# SCH.net
KiCad netlist of a schematic drawn in EasyEDA
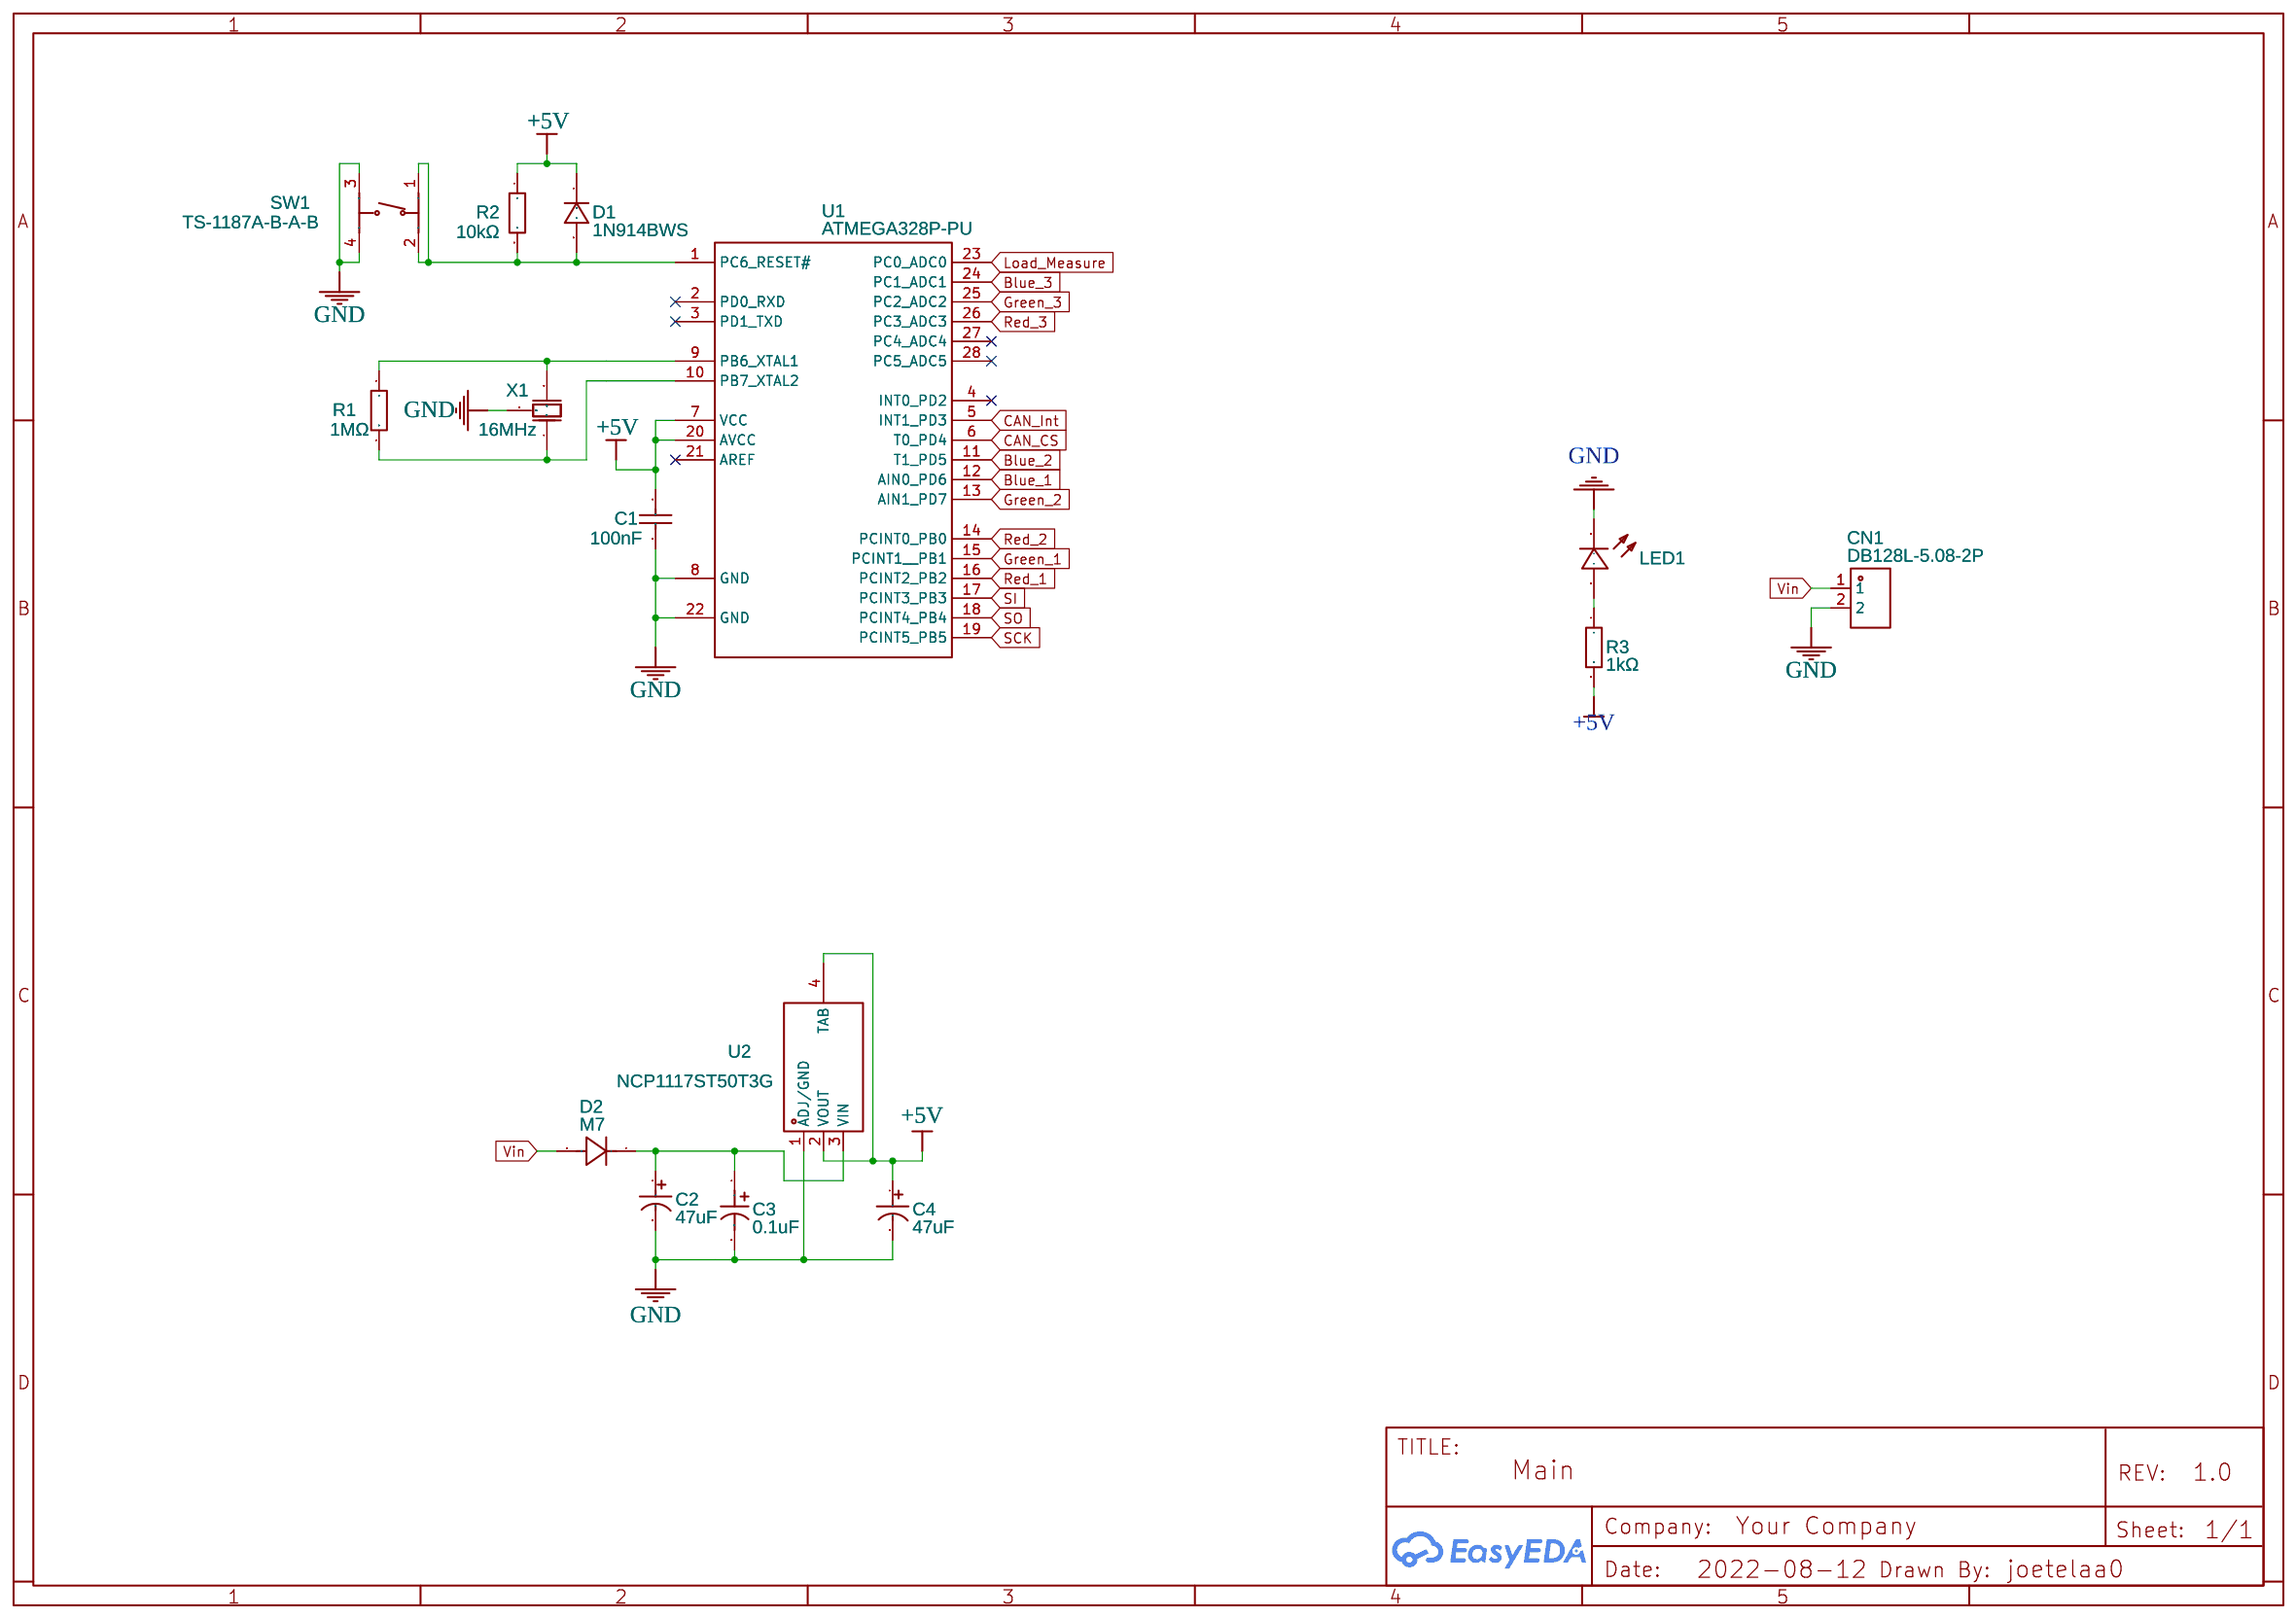
[diagram p0: Main]
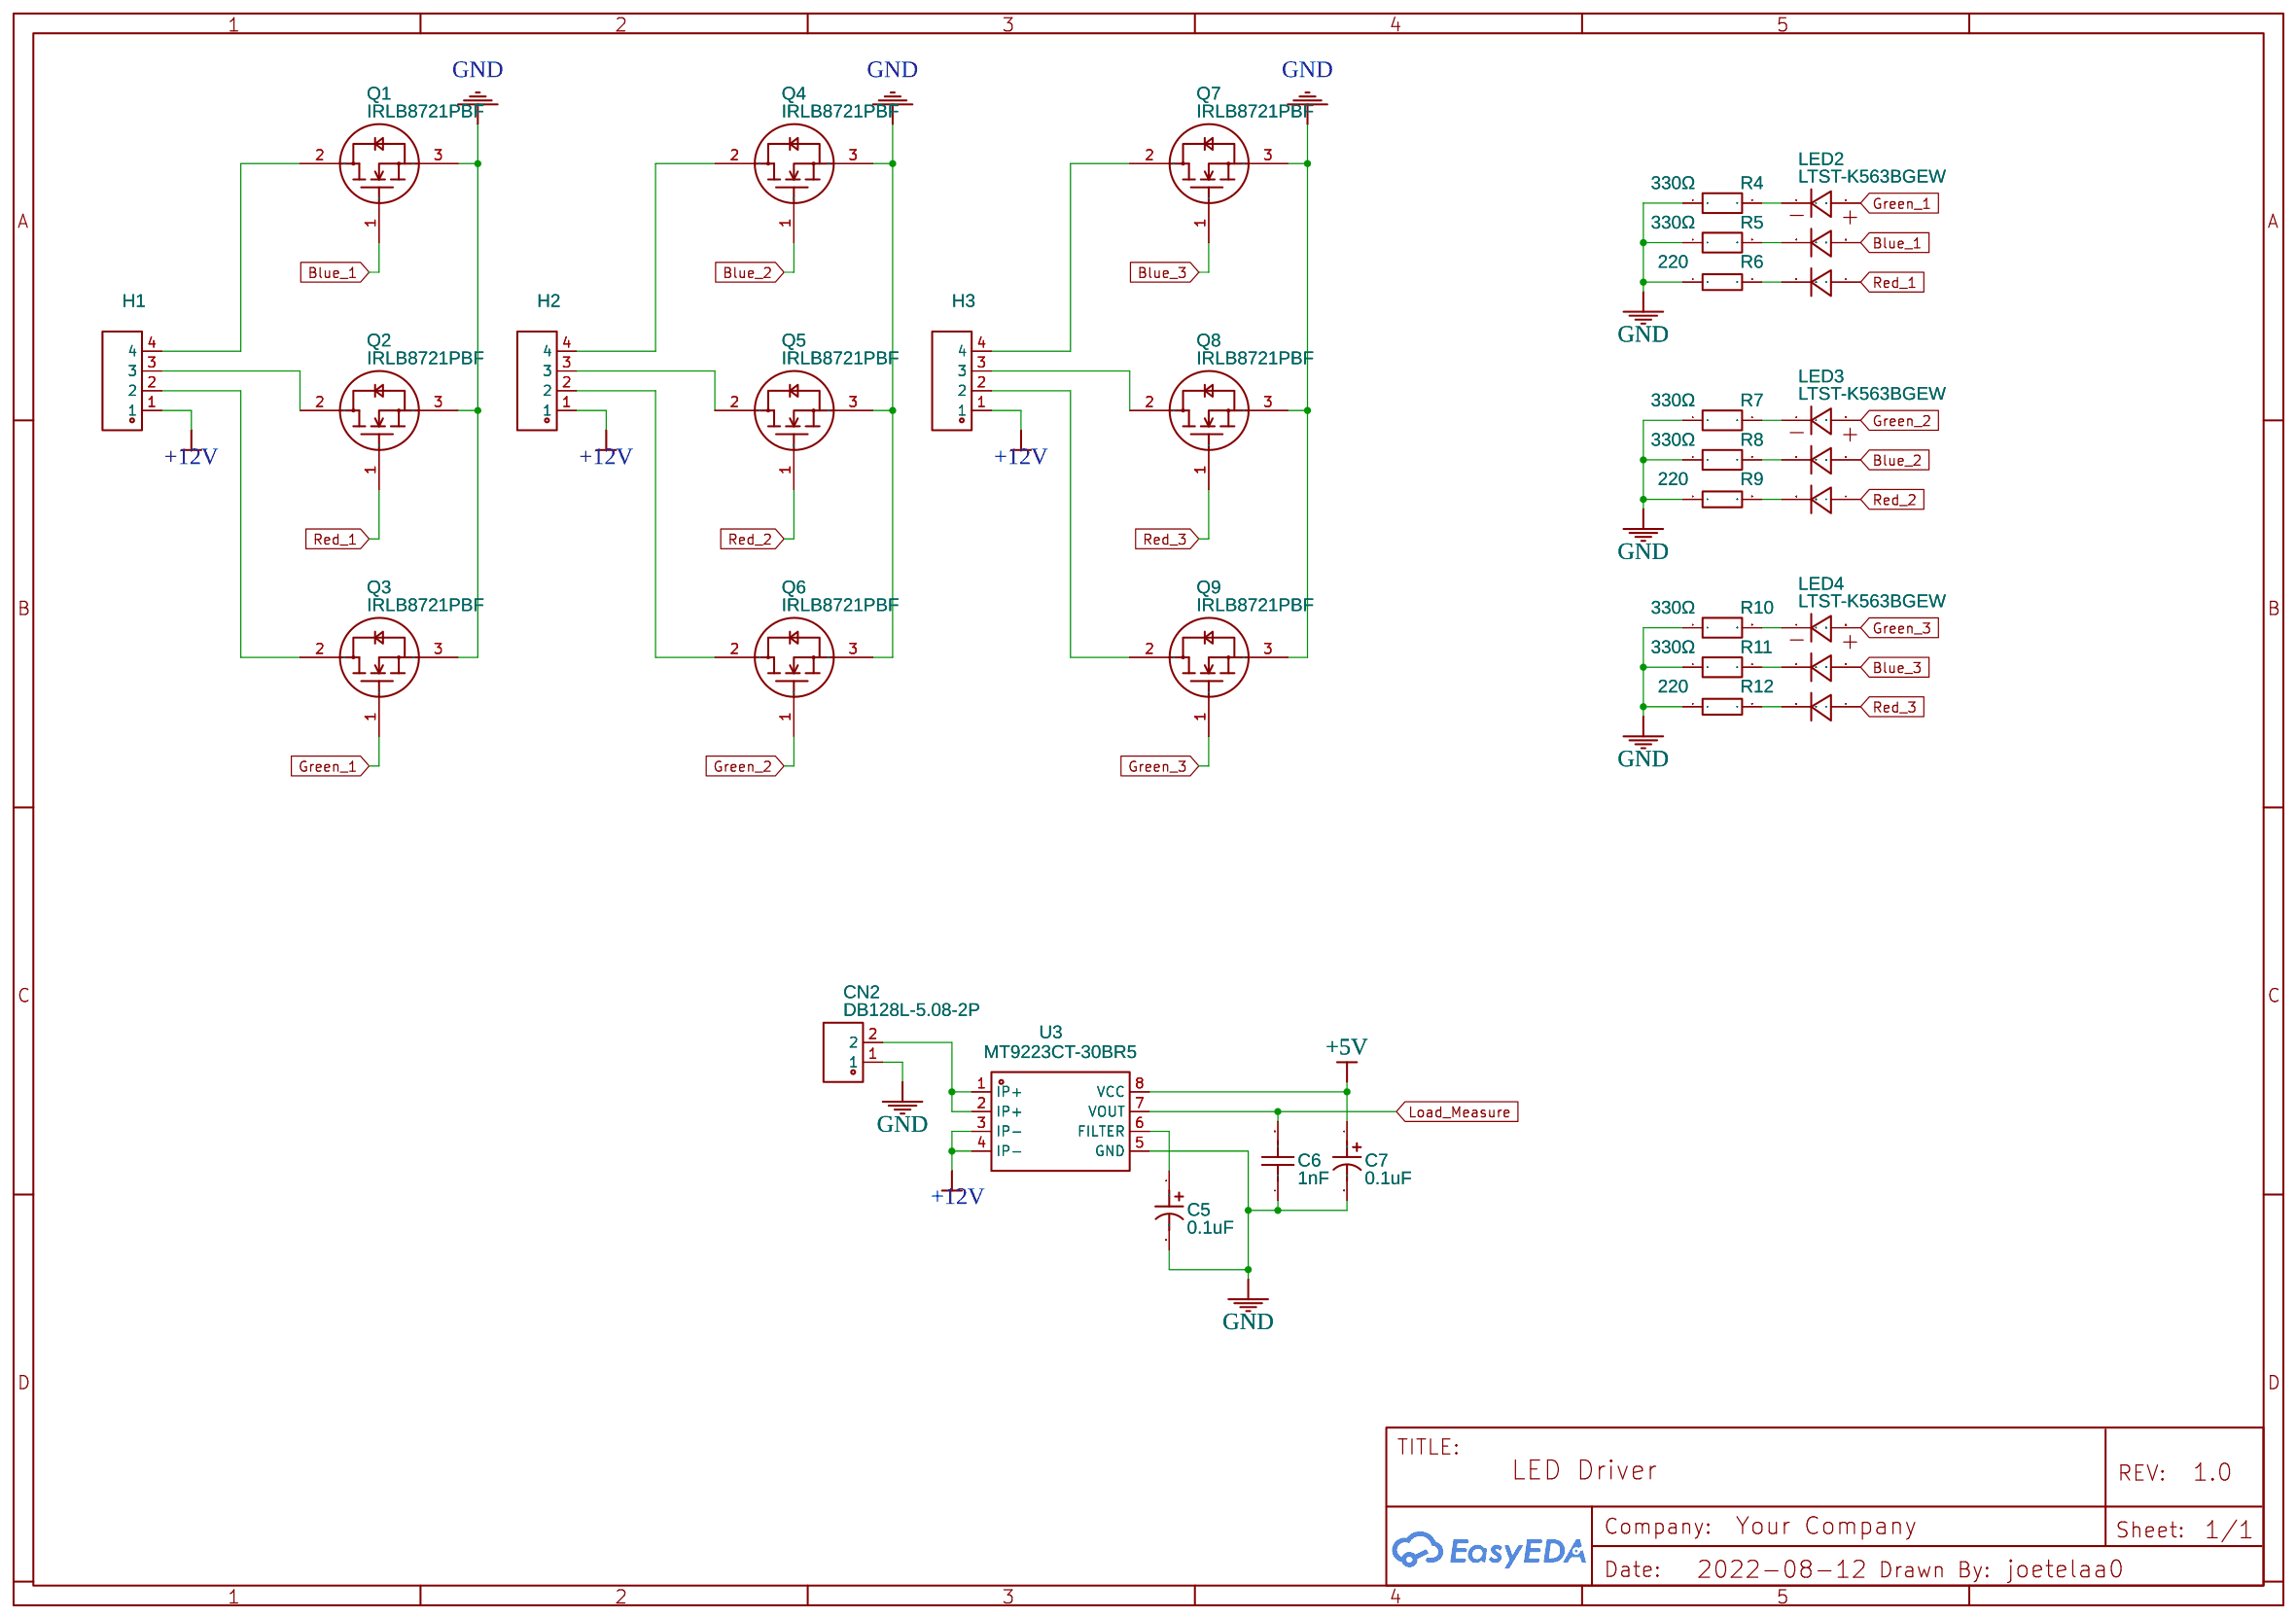
[diagram p1: LED Driver]
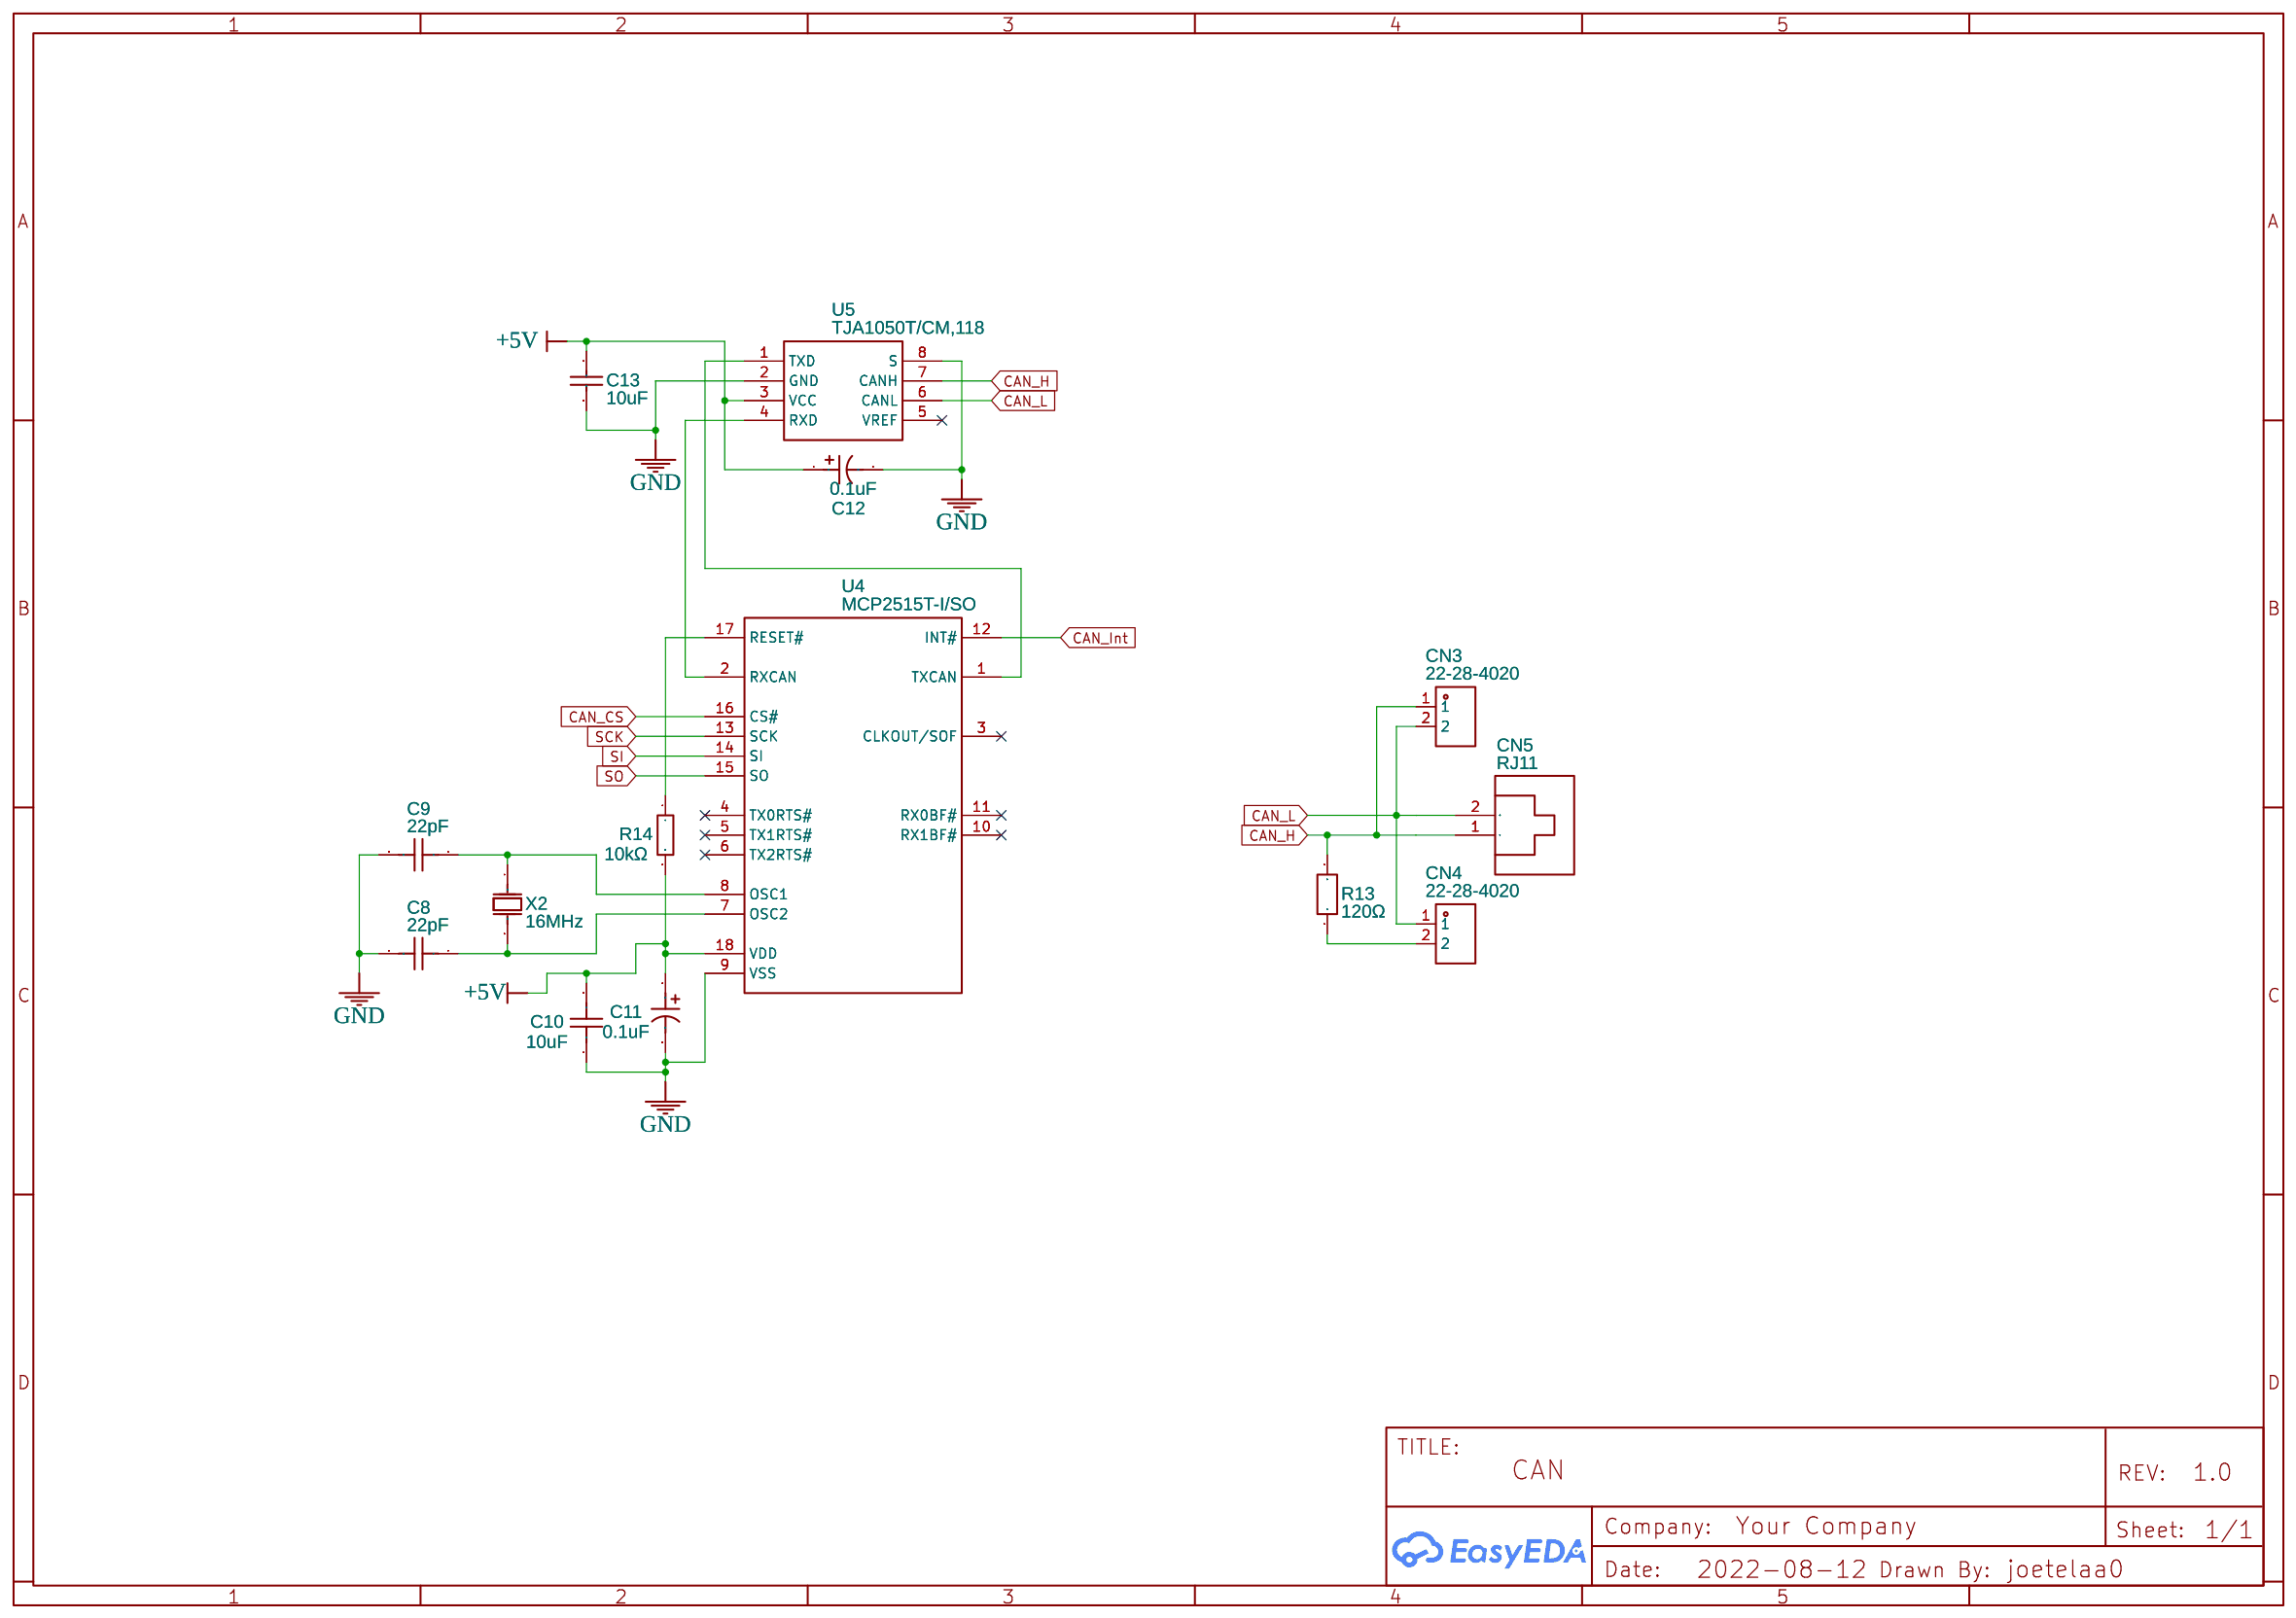
[diagram p2: CAN]

(export (version "E")
  (design (tool "Eeschema 10.0.6"))
  (components
    (comp (ref "C1")
      (value "100nF")
      (fields
        (field (name "BOM_Manufacturer Part") "FN18X104K500PBG")
        (field (name "BOM_Supplier Part") "C235731")
      )
      (libsource (lib "") (part "FN18X104K500PBG"))
    )
    (comp (ref "C2")
      (value "47uF")
      (fields
        (field (name "BOM_Manufacturer Part") "RVT1V470M0605")
        (field (name "BOM_Supplier Part") "C72522")
      )
      (libsource (lib "") (part "RVT1V470M0605_c72522"))
    )
    (comp (ref "C3")
      (value "0.1uF")
      (fields
        (field (name "BOM_Manufacturer Part") "CA45A-A-35V-0.1UF-K")
        (field (name "BOM_Supplier Part") "C2976899")
      )
      (libsource (lib "") (part "CA45A-A-35V-0.1UF-K"))
    )
    (comp (ref "C4")
      (value "47uF")
      (fields
        (field (name "BOM_Manufacturer Part") "RVT1V470M0605")
        (field (name "BOM_Supplier Part") "C72522")
      )
      (libsource (lib "") (part "RVT1V470M0605_c72522"))
    )
    (comp (ref "CN1")
      (value "DB128L-5.08-2P")
      (fields (field (name "BOM_Supplier Part") "C395868"))
      (libsource (lib "") (part "DB128L-5.08-2P"))
    )
    (comp (ref "D1")
      (value "1N914BWS")
      (fields (field (name "BOM_Supplier Part") "C258181"))
      (libsource (lib "") (part "1N914BWS"))
    )
    (comp (ref "D2")
      (value "M7")
      (fields (field (name "BOM_Manufacturer Part") "1N4007") (field (name "BOM_Supplier Part") "C727081"))
      (libsource (lib "") (part "1N4007_C727081"))
    )
    (comp (ref "LED1")
      (value "FC-1608GHK-570A08")
      (fields (field (name "BOM_Supplier Part") "C193901"))
      (libsource (lib "") (part "FC-1608GHK-570A08"))
    )
    (comp (ref "R1")
      (value "1MΩ")
      (fields
        (field (name "BOM_Manufacturer Part") "ERJ-3EKF1004V")
        (field (name "BOM_Supplier Part") "C193390")
      )
      (libsource (lib "") (part "ERJ-3EKF1004V"))
    )
    (comp (ref "R2")
      (value "10kΩ")
      (fields
        (field (name "BOM_Manufacturer Part") "RMS06FT1002")
        (field (name "BOM_Supplier Part") "C209013")
      )
      (libsource (lib "") (part "RMS06FT1002"))
    )
    (comp (ref "R3")
      (value "1kΩ")
      (fields
        (field (name "BOM_Manufacturer Part") "TR0603B1KP0525")
        (field (name "BOM_Supplier Part") "C188364")
      )
      (libsource (lib "") (part "TR0603B1KP0525"))
    )
    (comp (ref "SW1")
      (value "TS-1187A-B-A-B")
      (fields (field (name "BOM_Supplier Part") "C318884"))
      (libsource (lib "") (part "TS-1187A-B-A-B"))
    )
    (comp (ref "U1")
      (value "ATMEGA328P-PU")
      (fields (field (name "BOM_Supplier Part") "C33901"))
      (libsource (lib "") (part "ATMEGA328P-PU"))
    )
    (comp (ref "U2")
      (value "NCP1117ST50T3G")
      (fields (field (name "BOM_Supplier Part") "C17314"))
      (libsource (lib "") (part "NCP1117ST50T3G"))
    )
    (comp (ref "X1")
      (value "16MHz")
      (fields
        (field (name "BOM_Manufacturer Part") "CSTNE16M0V53C000R0")
        (field (name "BOM_Supplier Part") "C882606")
      )
      (libsource (lib "") (part "CSTNE16M0V53C000R0"))
    )
    (comp (ref "C5")
      (value "0.1uF")
      (fields
        (field (name "BOM_Manufacturer Part") "CA45A-A-35V-0.1UF-K")
        (field (name "BOM_Supplier Part") "C2976899")
      )
      (libsource (lib "") (part "CA45A-A-35V-0.1UF-K"))
    )
    (comp (ref "C6")
      (value "1nF")
      (fields
        (field (name "BOM_Manufacturer Part") "GRM1885C1H102JA01D")
        (field (name "BOM_Supplier Part") "C77026")
      )
      (libsource (lib "") (part "GRM1885C1H102JA01D"))
    )
    (comp (ref "C7")
      (value "0.1uF")
      (fields
        (field (name "BOM_Manufacturer Part") "CA45A-A-35V-0.1UF-K")
        (field (name "BOM_Supplier Part") "C2976899")
      )
      (libsource (lib "") (part "CA45A-A-35V-0.1UF-K"))
    )
    (comp (ref "CN2")
      (value "DB128L-5.08-2P")
      (fields (field (name "BOM_Supplier Part") "C395868"))
      (libsource (lib "") (part "DB128L-5.08-2P"))
    )
    (comp (ref "H1")
      (value "X6511WV-04H-C30D60")
      (fields (field (name "BOM_Supplier Part") "C706876"))
      (libsource (lib "") (part "X6511WV-04H-C30D60"))
    )
    (comp (ref "H2")
      (value "X6511WV-04H-C30D60")
      (fields (field (name "BOM_Supplier Part") "C706876"))
      (libsource (lib "") (part "X6511WV-04H-C30D60"))
    )
    (comp (ref "H3")
      (value "X6511WV-04H-C30D60")
      (fields (field (name "BOM_Supplier Part") "C706876"))
      (libsource (lib "") (part "X6511WV-04H-C30D60"))
    )
    (comp (ref "LED2")
      (value "LTST-K563BGEW")
      (fields (field (name "BOM_Supplier Part") "C284911"))
      (libsource (lib "") (part "LTST-K563BGEW"))
    )
    (comp (ref "LED3")
      (value "LTST-K563BGEW")
      (fields (field (name "BOM_Supplier Part") "C284911"))
      (libsource (lib "") (part "LTST-K563BGEW"))
    )
    (comp (ref "LED4")
      (value "LTST-K563BGEW")
      (fields (field (name "BOM_Supplier Part") "C284911"))
      (libsource (lib "") (part "LTST-K563BGEW"))
    )
    (comp (ref "Q1")
      (value "IRLB8721PBF")
      (fields (field (name "BOM_Supplier Part") "C153222"))
      (libsource (lib "") (part "IRLB8721PBF"))
    )
    (comp (ref "Q2")
      (value "IRLB8721PBF")
      (fields (field (name "BOM_Supplier Part") "C153222"))
      (libsource (lib "") (part "IRLB8721PBF"))
    )
    (comp (ref "Q3")
      (value "IRLB8721PBF")
      (fields (field (name "BOM_Supplier Part") "C153222"))
      (libsource (lib "") (part "IRLB8721PBF"))
    )
    (comp (ref "Q4")
      (value "IRLB8721PBF")
      (fields (field (name "BOM_Supplier Part") "C153222"))
      (libsource (lib "") (part "IRLB8721PBF"))
    )
    (comp (ref "Q5")
      (value "IRLB8721PBF")
      (fields (field (name "BOM_Supplier Part") "C153222"))
      (libsource (lib "") (part "IRLB8721PBF"))
    )
    (comp (ref "Q6")
      (value "IRLB8721PBF")
      (fields (field (name "BOM_Supplier Part") "C153222"))
      (libsource (lib "") (part "IRLB8721PBF"))
    )
    (comp (ref "Q7")
      (value "IRLB8721PBF")
      (fields (field (name "BOM_Supplier Part") "C153222"))
      (libsource (lib "") (part "IRLB8721PBF"))
    )
    (comp (ref "Q8")
      (value "IRLB8721PBF")
      (fields (field (name "BOM_Supplier Part") "C153222"))
      (libsource (lib "") (part "IRLB8721PBF"))
    )
    (comp (ref "Q9")
      (value "IRLB8721PBF")
      (fields (field (name "BOM_Supplier Part") "C153222"))
      (libsource (lib "") (part "IRLB8721PBF"))
    )
    (comp (ref "R4")
      (value "330Ω")
      (fields
        (field (name "BOM_Manufacturer Part") "FRC0603F3300TS")
        (field (name "BOM_Supplier Part") "C2933198")
      )
      (libsource (lib "") (part "FRC0603F3300TS"))
    )
    (comp (ref "R5")
      (value "330Ω")
      (fields
        (field (name "BOM_Manufacturer Part") "FRC0603F3300TS")
        (field (name "BOM_Supplier Part") "C2933198")
      )
      (libsource (lib "") (part "FRC0603F3300TS"))
    )
    (comp (ref "R6")
      (value "220")
      (fields
        (field (name "BOM_Manufacturer Part") "AF0603FR-07220RL")
        (field (name "BOM_Supplier Part") "C144094")
      )
      (libsource (lib "") (part "AF0603FR-07220RL"))
    )
    (comp (ref "R7")
      (value "330Ω")
      (fields
        (field (name "BOM_Manufacturer Part") "FRC0603F3300TS")
        (field (name "BOM_Supplier Part") "C2933198")
      )
      (libsource (lib "") (part "FRC0603F3300TS"))
    )
    (comp (ref "R8")
      (value "330Ω")
      (fields
        (field (name "BOM_Manufacturer Part") "FRC0603F3300TS")
        (field (name "BOM_Supplier Part") "C2933198")
      )
      (libsource (lib "") (part "FRC0603F3300TS"))
    )
    (comp (ref "R9")
      (value "220")
      (fields
        (field (name "BOM_Manufacturer Part") "AF0603FR-07220RL")
        (field (name "BOM_Supplier Part") "C144094")
      )
      (libsource (lib "") (part "AF0603FR-07220RL"))
    )
    (comp (ref "R10")
      (value "330Ω")
      (fields
        (field (name "BOM_Manufacturer Part") "FRC0603F3300TS")
        (field (name "BOM_Supplier Part") "C2933198")
      )
      (libsource (lib "") (part "FRC0603F3300TS"))
    )
    (comp (ref "R11")
      (value "330Ω")
      (fields
        (field (name "BOM_Manufacturer Part") "FRC0603F3300TS")
        (field (name "BOM_Supplier Part") "C2933198")
      )
      (libsource (lib "") (part "FRC0603F3300TS"))
    )
    (comp (ref "R12")
      (value "220")
      (fields
        (field (name "BOM_Manufacturer Part") "AF0603FR-07220RL")
        (field (name "BOM_Supplier Part") "C144094")
      )
      (libsource (lib "") (part "AF0603FR-07220RL"))
    )
    (comp (ref "U3")
      (value "MT9223CT-30BR5")
      (fields (field (name "BOM_Supplier Part") "C879636"))
      (libsource (lib "") (part "MT9223CT-30BR5"))
    )
    (comp (ref "C8")
      (value "22pF")
      (fields
        (field (name "BOM_Manufacturer Part") "CGA3E2C0G1H220JT0Y0N")
        (field (name "BOM_Supplier Part") "C338053")
      )
      (libsource (lib "") (part "CGA3E2C0G1H220JT0Y0N"))
    )
    (comp (ref "C9")
      (value "22pF")
      (fields
        (field (name "BOM_Manufacturer Part") "CGA3E2C0G1H220JT0Y0N")
        (field (name "BOM_Supplier Part") "C338053")
      )
      (libsource (lib "") (part "CGA3E2C0G1H220JT0Y0N"))
    )
    (comp (ref "C10")
      (value "10uF")
      (fields
        (field (name "BOM_Manufacturer Part") "JMK316AB7106KLHT")
        (field (name "BOM_Supplier Part") "C454108")
      )
      (libsource (lib "") (part "JMK316AB7106KLHT"))
    )
    (comp (ref "C11")
      (value "0.1uF")
      (fields
        (field (name "BOM_Manufacturer Part") "CA45A-A-35V-0.1UF-K")
        (field (name "BOM_Supplier Part") "C2976899")
      )
      (libsource (lib "") (part "CA45A-A-35V-0.1UF-K"))
    )
    (comp (ref "C12")
      (value "0.1uF")
      (fields
        (field (name "BOM_Manufacturer Part") "CA45A-A-35V-0.1UF-K")
        (field (name "BOM_Supplier Part") "C2976899")
      )
      (libsource (lib "") (part "CA45A-A-35V-0.1UF-K_1"))
    )
    (comp (ref "C13")
      (value "10uF")
      (fields
        (field (name "BOM_Manufacturer Part") "JMK107BJ106MA-T")
        (field (name "BOM_Supplier Part") "C87152")
      )
      (libsource (lib "") (part "JMK107BJ106MA-T"))
    )
    (comp (ref "CN3")
      (value "22-28-4020")
      (fields (field (name "BOM_Supplier Part") "C234182"))
      (libsource (lib "") (part "22-28-4020"))
    )
    (comp (ref "CN4")
      (value "22-28-4020")
      (fields (field (name "BOM_Supplier Part") "C234182"))
      (libsource (lib "") (part "22-28-4020"))
    )
    (comp (ref "CN5")
      (value "RJ11")
      (fields (field (name "BOM_Supplier Part") "C189745"))
      (libsource (lib "") (part "PCB-6P2C-90_C189745"))
    )
    (comp (ref "R13")
      (value "120Ω")
      (fields
        (field (name "BOM_Manufacturer Part") "ERJPA3J121V")
        (field (name "BOM_Supplier Part") "C445808")
      )
      (libsource (lib "") (part "ERJPA3J121V"))
    )
    (comp (ref "R14")
      (value "10kΩ")
      (fields
        (field (name "BOM_Manufacturer Part") "RMS06FT1002")
        (field (name "BOM_Supplier Part") "C209013")
      )
      (libsource (lib "") (part "RMS06FT1002"))
    )
    (comp (ref "U4")
      (value "MCP2515T-I/SO")
      (fields (field (name "BOM_Supplier Part") "C153782"))
      (libsource (lib "") (part "MCP2515T-I/SO"))
    )
    (comp (ref "U5")
      (value "TJA1050T/CM,118")
      (fields (field (name "BOM_Supplier Part") "C6952"))
      (libsource (lib "") (part "TJA1050T/CM,118"))
    )
    (comp (ref "X2")
      (value "16MHz")
      (fields
        (field (name "BOM_Manufacturer Part") "X49SD16MSD2SC")
        (field (name "BOM_Supplier Part") "C16212")
      )
      (libsource (lib "") (part "X49SD16MSD2SC"))
    )
  )
  (nets
    (net (code "1") (name "+5V") (class "Default")
      (node (ref "C1") (pin "2") (pinfunction "2_2") (pintype "input"))
      (node (ref "C10") (pin "2") (pinfunction "2_2") (pintype "unspecified"))
      (node (ref "C11") (pin "1") (pinfunction "1_1") (pintype "input"))
      (node (ref "C12") (pin "1") (pinfunction "1_1") (pintype "input"))
      (node (ref "C13") (pin "2") (pinfunction "2_2") (pintype "input"))
      (node (ref "C4") (pin "1") (pinfunction "1_1") (pintype "input"))
      (node (ref "C7") (pin "1") (pinfunction "1_1") (pintype "input"))
      (node (ref "D1") (pin "1") (pinfunction "C_1") (pintype "unspecified"))
      (node (ref "R14") (pin "2") (pinfunction "2_2") (pintype "unspecified"))
      (node (ref "R2") (pin "1") (pinfunction "1_1") (pintype "unspecified"))
      (node (ref "R3") (pin "2") (pinfunction "2_2") (pintype "unspecified"))
      (node (ref "U1") (pin "20") (pinfunction "AVCC_20") (pintype "passive"))
      (node (ref "U1") (pin "7") (pinfunction "VCC_7") (pintype "passive"))
      (node (ref "U2") (pin "2") (pinfunction "VOUT_2") (pintype "unspecified"))
      (node (ref "U2") (pin "4") (pinfunction "TAB_4") (pintype "unspecified"))
      (node (ref "U3") (pin "8") (pinfunction "VCC_8") (pintype "unspecified"))
      (node (ref "U4") (pin "18") (pinfunction "VDD_18") (pintype "passive"))
      (node (ref "U5") (pin "3") (pinfunction "VCC_3") (pintype "unspecified"))
    )
    (net (code "2") (name "+12V") (class "Default")
      (node (ref "H1") (pin "1") (pinfunction "1_1") (pintype "unspecified"))
      (node (ref "H2") (pin "1") (pinfunction "1_1") (pintype "unspecified"))
      (node (ref "H3") (pin "1") (pinfunction "1_1") (pintype "unspecified"))
      (node (ref "U3") (pin "3") (pinfunction "IP-_3") (pintype "unspecified"))
      (node (ref "U3") (pin "4") (pinfunction "IP-_4") (pintype "unspecified"))
    )
    (net (code "3") (name "Blue_1") (class "Default")
      (node (ref "LED2") (pin "5") (pinfunction "5_5") (pintype "unspecified"))
      (node (ref "Q1") (pin "1") (pinfunction "G_1") (pintype "unspecified"))
      (node (ref "U1") (pin "12") (pinfunction "AIN0_PD6_12") (pintype "bidirectional"))
    )
    (net (code "4") (name "Blue_2") (class "Default")
      (node (ref "LED3") (pin "5") (pinfunction "5_5") (pintype "unspecified"))
      (node (ref "Q4") (pin "1") (pinfunction "G_1") (pintype "unspecified"))
      (node (ref "U1") (pin "11") (pinfunction "T1_PD5_11") (pintype "bidirectional"))
    )
    (net (code "5") (name "Blue_3") (class "Default")
      (node (ref "LED4") (pin "5") (pinfunction "5_5") (pintype "unspecified"))
      (node (ref "Q7") (pin "1") (pinfunction "G_1") (pintype "unspecified"))
      (node (ref "U1") (pin "24") (pinfunction "PC1_ADC1_24") (pintype "bidirectional"))
    )
    (net (code "6") (name "CAN_CS") (class "Default")
      (node (ref "U1") (pin "6") (pinfunction "T0_PD4_6") (pintype "bidirectional"))
      (node (ref "U4") (pin "16") (pinfunction "CS#_16") (pintype "unspecified"))
    )
    (net (code "7") (name "CAN_H") (class "Default")
      (node (ref "CN3") (pin "1") (pinfunction "1_1") (pintype "unspecified"))
      (node (ref "CN5") (pin "1") (pinfunction "1_1") (pintype "unspecified"))
      (node (ref "R13") (pin "2") (pinfunction "2_2") (pintype "unspecified"))
      (node (ref "U5") (pin "7") (pinfunction "CANH_7") (pintype "unspecified"))
    )
    (net (code "8") (name "CAN_Int") (class "Default")
      (node (ref "U1") (pin "5") (pinfunction "INT1_PD3_5") (pintype "bidirectional"))
      (node (ref "U4") (pin "12") (pinfunction "INT#_12") (pintype "output"))
    )
    (net (code "9") (name "CAN_L") (class "Default")
      (node (ref "CN3") (pin "2") (pinfunction "2_2") (pintype "unspecified"))
      (node (ref "CN4") (pin "1") (pinfunction "1_1") (pintype "unspecified"))
      (node (ref "CN5") (pin "2") (pinfunction "2_2") (pintype "unspecified"))
      (node (ref "U5") (pin "6") (pinfunction "CANL_6") (pintype "unspecified"))
    )
    (net (code "10") (name "GND") (class "Default")
      (node (ref "C1") (pin "1") (pinfunction "1_1") (pintype "input"))
      (node (ref "C10") (pin "1") (pinfunction "1_1") (pintype "unspecified"))
      (node (ref "C11") (pin "2") (pinfunction "2_2") (pintype "input"))
      (node (ref "C12") (pin "2") (pinfunction "2_2") (pintype "input"))
      (node (ref "C13") (pin "1") (pinfunction "1_1") (pintype "input"))
      (node (ref "C2") (pin "2") (pinfunction "2_2") (pintype "input"))
      (node (ref "C3") (pin "2") (pinfunction "2_2") (pintype "input"))
      (node (ref "C4") (pin "2") (pinfunction "2_2") (pintype "input"))
      (node (ref "C5") (pin "2") (pinfunction "2_2") (pintype "input"))
      (node (ref "C6") (pin "1") (pinfunction "1_1") (pintype "unspecified"))
      (node (ref "C7") (pin "2") (pinfunction "2_2") (pintype "input"))
      (node (ref "C8") (pin "2") (pinfunction "2_2") (pintype "unspecified"))
      (node (ref "C9") (pin "2") (pinfunction "2_2") (pintype "unspecified"))
      (node (ref "CN1") (pin "2") (pinfunction "2_2") (pintype "unspecified"))
      (node (ref "CN2") (pin "1") (pinfunction "1_1") (pintype "unspecified"))
      (node (ref "LED1") (pin "2") (pinfunction "-_2") (pintype "unspecified"))
      (node (ref "Q1") (pin "3") (pinfunction "S_3") (pintype "unspecified"))
      (node (ref "Q2") (pin "3") (pinfunction "S_3") (pintype "unspecified"))
      (node (ref "Q3") (pin "3") (pinfunction "S_3") (pintype "unspecified"))
      (node (ref "Q4") (pin "3") (pinfunction "S_3") (pintype "unspecified"))
      (node (ref "Q5") (pin "3") (pinfunction "S_3") (pintype "unspecified"))
      (node (ref "Q6") (pin "3") (pinfunction "S_3") (pintype "unspecified"))
      (node (ref "Q7") (pin "3") (pinfunction "S_3") (pintype "unspecified"))
      (node (ref "Q8") (pin "3") (pinfunction "S_3") (pintype "unspecified"))
      (node (ref "Q9") (pin "3") (pinfunction "S_3") (pintype "unspecified"))
      (node (ref "R10") (pin "1") (pinfunction "1_1") (pintype "unspecified"))
      (node (ref "R11") (pin "1") (pinfunction "1_1") (pintype "unspecified"))
      (node (ref "R12") (pin "1") (pinfunction "1_1") (pintype "unspecified"))
      (node (ref "R4") (pin "1") (pinfunction "1_1") (pintype "unspecified"))
      (node (ref "R5") (pin "1") (pinfunction "1_1") (pintype "unspecified"))
      (node (ref "R6") (pin "1") (pinfunction "1_1") (pintype "unspecified"))
      (node (ref "R7") (pin "1") (pinfunction "1_1") (pintype "unspecified"))
      (node (ref "R8") (pin "1") (pinfunction "1_1") (pintype "unspecified"))
      (node (ref "R9") (pin "1") (pinfunction "1_1") (pintype "unspecified"))
      (node (ref "SW1") (pin "3") (pinfunction "C_3") (pintype "unspecified"))
      (node (ref "SW1") (pin "4") (pinfunction "D_4") (pintype "unspecified"))
      (node (ref "U1") (pin "22") (pinfunction "GND_22") (pintype "passive"))
      (node (ref "U1") (pin "8") (pinfunction "GND_8") (pintype "passive"))
      (node (ref "U2") (pin "1") (pinfunction "ADJ/GND_1") (pintype "unspecified"))
      (node (ref "U3") (pin "5") (pinfunction "GND_5") (pintype "unspecified"))
      (node (ref "U4") (pin "9") (pinfunction "VSS_9") (pintype "passive"))
      (node (ref "U5") (pin "2") (pinfunction "GND_2") (pintype "unspecified"))
      (node (ref "U5") (pin "8") (pinfunction "S_8") (pintype "unspecified"))
      (node (ref "X1") (pin "2") (pinfunction "GND_2") (pintype "input"))
    )
    (net (code "11") (name "Green_1") (class "Default")
      (node (ref "LED2") (pin "6") (pinfunction "6_6") (pintype "unspecified"))
      (node (ref "Q3") (pin "1") (pinfunction "G_1") (pintype "unspecified"))
      (node (ref "U1") (pin "15") (pinfunction "PCINT1__PB1_15") (pintype "bidirectional"))
    )
    (net (code "12") (name "Green_2") (class "Default")
      (node (ref "LED3") (pin "6") (pinfunction "6_6") (pintype "unspecified"))
      (node (ref "Q6") (pin "1") (pinfunction "G_1") (pintype "unspecified"))
      (node (ref "U1") (pin "13") (pinfunction "AIN1_PD7_13") (pintype "bidirectional"))
    )
    (net (code "13") (name "Green_3") (class "Default")
      (node (ref "LED4") (pin "6") (pinfunction "6_6") (pintype "unspecified"))
      (node (ref "Q9") (pin "1") (pinfunction "G_1") (pintype "unspecified"))
      (node (ref "U1") (pin "25") (pinfunction "PC2_ADC2_25") (pintype "bidirectional"))
    )
    (net (code "14") (name "Load_Measure") (class "Default")
      (node (ref "C6") (pin "2") (pinfunction "2_2") (pintype "unspecified"))
      (node (ref "U1") (pin "23") (pinfunction "PC0_ADC0_23") (pintype "bidirectional"))
      (node (ref "U3") (pin "7") (pinfunction "VOUT_7") (pintype "unspecified"))
    )
    (net (code "15") (name "Net-(CN2-Pad2)") (class "Default")
      (node (ref "CN2") (pin "2") (pinfunction "2_2") (pintype "unspecified"))
      (node (ref "U3") (pin "1") (pinfunction "IP+_1") (pintype "unspecified"))
      (node (ref "U3") (pin "2") (pinfunction "IP+_2") (pintype "unspecified"))
    )
    (net (code "16") (name "Net-(CN4-Pad2)") (class "Default")
      (node (ref "CN4") (pin "2") (pinfunction "2_2") (pintype "unspecified"))
      (node (ref "R13") (pin "1") (pinfunction "1_1") (pintype "unspecified"))
    )
    (net (code "17") (name "Net-(D1-A)") (class "Default")
      (node (ref "D1") (pin "2") (pinfunction "A_2") (pintype "unspecified"))
      (node (ref "R2") (pin "2") (pinfunction "2_2") (pintype "unspecified"))
      (node (ref "SW1") (pin "1") (pinfunction "A_1") (pintype "unspecified"))
      (node (ref "SW1") (pin "2") (pinfunction "B_2") (pintype "unspecified"))
      (node (ref "U1") (pin "1") (pinfunction "PC6_RESET#_1") (pintype "bidirectional"))
    )
    (net (code "18") (name "Net-(D2-K)") (class "Default")
      (node (ref "C2") (pin "1") (pinfunction "1_1") (pintype "input"))
      (node (ref "C3") (pin "1") (pinfunction "1_1") (pintype "input"))
      (node (ref "D2") (pin "1") (pinfunction "K_1") (pintype "unspecified"))
      (node (ref "U2") (pin "3") (pinfunction "VIN_3") (pintype "unspecified"))
    )
    (net (code "19") (name "Net-(LED1-+)") (class "Default")
      (node (ref "LED1") (pin "1") (pinfunction "+_1") (pintype "unspecified"))
      (node (ref "R3") (pin "1") (pinfunction "1_1") (pintype "unspecified"))
    )
    (net (code "20") (name "Net-(LED2-Pad1)") (class "Default")
      (node (ref "LED2") (pin "1") (pinfunction "1_1") (pintype "unspecified"))
      (node (ref "R4") (pin "2") (pinfunction "2_2") (pintype "unspecified"))
    )
    (net (code "21") (name "Net-(LED2-Pad2)") (class "Default")
      (node (ref "LED2") (pin "2") (pinfunction "2_2") (pintype "unspecified"))
      (node (ref "R5") (pin "2") (pinfunction "2_2") (pintype "unspecified"))
    )
    (net (code "22") (name "Net-(LED2-Pad3)") (class "Default")
      (node (ref "LED2") (pin "3") (pinfunction "3_3") (pintype "unspecified"))
      (node (ref "R6") (pin "2") (pinfunction "2_2") (pintype "unspecified"))
    )
    (net (code "23") (name "Net-(LED3-Pad1)") (class "Default")
      (node (ref "LED3") (pin "1") (pinfunction "1_1") (pintype "unspecified"))
      (node (ref "R7") (pin "2") (pinfunction "2_2") (pintype "unspecified"))
    )
    (net (code "24") (name "Net-(LED3-Pad2)") (class "Default")
      (node (ref "LED3") (pin "2") (pinfunction "2_2") (pintype "unspecified"))
      (node (ref "R8") (pin "2") (pinfunction "2_2") (pintype "unspecified"))
    )
    (net (code "25") (name "Net-(LED3-Pad3)") (class "Default")
      (node (ref "LED3") (pin "3") (pinfunction "3_3") (pintype "unspecified"))
      (node (ref "R9") (pin "2") (pinfunction "2_2") (pintype "unspecified"))
    )
    (net (code "26") (name "Net-(LED4-Pad1)") (class "Default")
      (node (ref "LED4") (pin "1") (pinfunction "1_1") (pintype "unspecified"))
      (node (ref "R10") (pin "2") (pinfunction "2_2") (pintype "unspecified"))
    )
    (net (code "27") (name "Net-(LED4-Pad2)") (class "Default")
      (node (ref "LED4") (pin "2") (pinfunction "2_2") (pintype "unspecified"))
      (node (ref "R11") (pin "2") (pinfunction "2_2") (pintype "unspecified"))
    )
    (net (code "28") (name "Net-(LED4-Pad3)") (class "Default")
      (node (ref "LED4") (pin "3") (pinfunction "3_3") (pintype "unspecified"))
      (node (ref "R12") (pin "2") (pinfunction "2_2") (pintype "unspecified"))
    )
    (net (code "29") (name "Net-(Q1-D)") (class "Default")
      (node (ref "H1") (pin "4") (pinfunction "4_4") (pintype "unspecified"))
      (node (ref "Q1") (pin "2") (pinfunction "D_2") (pintype "unspecified"))
    )
    (net (code "30") (name "Net-(Q2-D)") (class "Default")
      (node (ref "H1") (pin "3") (pinfunction "3_3") (pintype "unspecified"))
      (node (ref "Q2") (pin "2") (pinfunction "D_2") (pintype "unspecified"))
    )
    (net (code "31") (name "Net-(Q3-D)") (class "Default")
      (node (ref "H1") (pin "2") (pinfunction "2_2") (pintype "unspecified"))
      (node (ref "Q3") (pin "2") (pinfunction "D_2") (pintype "unspecified"))
    )
    (net (code "32") (name "Net-(Q4-D)") (class "Default")
      (node (ref "H2") (pin "4") (pinfunction "4_4") (pintype "unspecified"))
      (node (ref "Q4") (pin "2") (pinfunction "D_2") (pintype "unspecified"))
    )
    (net (code "33") (name "Net-(Q5-D)") (class "Default")
      (node (ref "H2") (pin "3") (pinfunction "3_3") (pintype "unspecified"))
      (node (ref "Q5") (pin "2") (pinfunction "D_2") (pintype "unspecified"))
    )
    (net (code "34") (name "Net-(Q6-D)") (class "Default")
      (node (ref "H2") (pin "2") (pinfunction "2_2") (pintype "unspecified"))
      (node (ref "Q6") (pin "2") (pinfunction "D_2") (pintype "unspecified"))
    )
    (net (code "35") (name "Net-(Q7-D)") (class "Default")
      (node (ref "H3") (pin "4") (pinfunction "4_4") (pintype "unspecified"))
      (node (ref "Q7") (pin "2") (pinfunction "D_2") (pintype "unspecified"))
    )
    (net (code "36") (name "Net-(Q8-D)") (class "Default")
      (node (ref "H3") (pin "3") (pinfunction "3_3") (pintype "unspecified"))
      (node (ref "Q8") (pin "2") (pinfunction "D_2") (pintype "unspecified"))
    )
    (net (code "37") (name "Net-(Q9-D)") (class "Default")
      (node (ref "H3") (pin "2") (pinfunction "2_2") (pintype "unspecified"))
      (node (ref "Q9") (pin "2") (pinfunction "D_2") (pintype "unspecified"))
    )
    (net (code "38") (name "Net-(U1-PB6_XTAL1)") (class "Default")
      (node (ref "R1") (pin "1") (pinfunction "1_1") (pintype "unspecified"))
      (node (ref "U1") (pin "9") (pinfunction "PB6_XTAL1_9") (pintype "bidirectional"))
      (node (ref "X1") (pin "3") (pinfunction "OSC2_3") (pintype "input"))
    )
    (net (code "39") (name "Net-(U1-PB7_XTAL2)") (class "Default")
      (node (ref "R1") (pin "2") (pinfunction "2_2") (pintype "unspecified"))
      (node (ref "U1") (pin "10") (pinfunction "PB7_XTAL2_10") (pintype "bidirectional"))
      (node (ref "X1") (pin "1") (pinfunction "OSC1_1") (pintype "input"))
    )
    (net (code "40") (name "Net-(U3-FILTER)") (class "Default")
      (node (ref "C5") (pin "1") (pinfunction "1_1") (pintype "input"))
      (node (ref "U3") (pin "6") (pinfunction "FILTER_6") (pintype "unspecified"))
    )
    (net (code "41") (name "Net-(U4-OSC1)") (class "Default")
      (node (ref "C9") (pin "1") (pinfunction "1_1") (pintype "unspecified"))
      (node (ref "U4") (pin "8") (pinfunction "OSC1_8") (pintype "unspecified"))
      (node (ref "X2") (pin "1") (pinfunction "OSC1_1") (pintype "input"))
    )
    (net (code "42") (name "Net-(U4-OSC2)") (class "Default")
      (node (ref "C8") (pin "1") (pinfunction "1_1") (pintype "unspecified"))
      (node (ref "U4") (pin "7") (pinfunction "OSC2_7") (pintype "output"))
      (node (ref "X2") (pin "2") (pinfunction "OSC2_2") (pintype "input"))
    )
    (net (code "43") (name "Net-(U4-RESET#)") (class "Default")
      (node (ref "R14") (pin "1") (pinfunction "1_1") (pintype "unspecified"))
      (node (ref "U4") (pin "17") (pinfunction "RESET#_17") (pintype "unspecified"))
    )
    (net (code "44") (name "Net-(U4-RXCAN)") (class "Default")
      (node (ref "U4") (pin "2") (pinfunction "RXCAN_2") (pintype "unspecified"))
      (node (ref "U5") (pin "4") (pinfunction "RXD_4") (pintype "unspecified"))
    )
    (net (code "45") (name "Net-(U4-TXCAN)") (class "Default")
      (node (ref "U4") (pin "1") (pinfunction "TXCAN_1") (pintype "output"))
      (node (ref "U5") (pin "1") (pinfunction "TXD_1") (pintype "unspecified"))
    )
    (net (code "46") (name "Red_1") (class "Default")
      (node (ref "LED2") (pin "4") (pinfunction "4_4") (pintype "unspecified"))
      (node (ref "Q2") (pin "1") (pinfunction "G_1") (pintype "unspecified"))
      (node (ref "U1") (pin "16") (pinfunction "PCINT2_PB2_16") (pintype "bidirectional"))
    )
    (net (code "47") (name "Red_2") (class "Default")
      (node (ref "LED3") (pin "4") (pinfunction "4_4") (pintype "unspecified"))
      (node (ref "Q5") (pin "1") (pinfunction "G_1") (pintype "unspecified"))
      (node (ref "U1") (pin "14") (pinfunction "PCINT0_PB0_14") (pintype "bidirectional"))
    )
    (net (code "48") (name "Red_3") (class "Default")
      (node (ref "LED4") (pin "4") (pinfunction "4_4") (pintype "unspecified"))
      (node (ref "Q8") (pin "1") (pinfunction "G_1") (pintype "unspecified"))
      (node (ref "U1") (pin "26") (pinfunction "PC3_ADC3_26") (pintype "bidirectional"))
    )
    (net (code "49") (name "SCK") (class "Default")
      (node (ref "U1") (pin "19") (pinfunction "PCINT5_PB5_19") (pintype "bidirectional"))
      (node (ref "U4") (pin "13") (pinfunction "SCK_13") (pintype "unspecified"))
    )
    (net (code "50") (name "SI") (class "Default")
      (node (ref "U1") (pin "17") (pinfunction "PCINT3_PB3_17") (pintype "bidirectional"))
      (node (ref "U4") (pin "14") (pinfunction "SI_14") (pintype "unspecified"))
    )
    (net (code "51") (name "SO") (class "Default")
      (node (ref "U1") (pin "18") (pinfunction "PCINT4_PB4_18") (pintype "bidirectional"))
      (node (ref "U4") (pin "15") (pinfunction "SO_15") (pintype "output"))
    )
    (net (code "52") (name "Vin") (class "Default")
      (node (ref "CN1") (pin "1") (pinfunction "1_1") (pintype "unspecified"))
      (node (ref "D2") (pin "2") (pinfunction "A_2") (pintype "unspecified"))
    )
    (net (code "53") (name "unconnected-(U1-AREF-Pad21)") (class "Default")
      (node (ref "U1") (pin "21") (pinfunction "AREF_21") (pintype "passive+no_connect"))
    )
    (net (code "54") (name "unconnected-(U1-INT0_PD2-Pad4)") (class "Default")
      (node (ref "U1") (pin "4") (pinfunction "INT0_PD2_4") (pintype "bidirectional+no_connect"))
    )
    (net (code "55") (name "unconnected-(U1-PC4_ADC4-Pad27)") (class "Default")
      (node (ref "U1") (pin "27") (pinfunction "PC4_ADC4_27") (pintype "bidirectional+no_connect"))
    )
    (net (code "56") (name "unconnected-(U1-PC5_ADC5-Pad28)") (class "Default")
      (node (ref "U1") (pin "28") (pinfunction "PC5_ADC5_28") (pintype "bidirectional+no_connect"))
    )
    (net (code "57") (name "unconnected-(U1-PD0_RXD-Pad2)") (class "Default")
      (node (ref "U1") (pin "2") (pinfunction "PD0_RXD_2") (pintype "bidirectional+no_connect"))
    )
    (net (code "58") (name "unconnected-(U1-PD1_TXD-Pad3)") (class "Default")
      (node (ref "U1") (pin "3") (pinfunction "PD1_TXD_3") (pintype "bidirectional+no_connect"))
    )
    (net (code "59") (name "unconnected-(U4-CLKOUT{slash}SOF-Pad3)") (class "Default")
      (node (ref "U4") (pin "3") (pinfunction "CLKOUT/SOF_3") (pintype "output+no_connect"))
    )
    (net (code "60") (name "unconnected-(U4-RX0BF#-Pad11)") (class "Default")
      (node (ref "U4") (pin "11") (pinfunction "RX0BF#_11") (pintype "output+no_connect"))
    )
    (net (code "61") (name "unconnected-(U4-RX1BF#-Pad10)") (class "Default")
      (node (ref "U4") (pin "10") (pinfunction "RX1BF#_10") (pintype "output+no_connect"))
    )
    (net (code "62") (name "unconnected-(U4-TX0RTS#-Pad4)") (class "Default")
      (node (ref "U4") (pin "4") (pinfunction "TX0RTS#_4") (pintype "unspecified+no_connect"))
    )
    (net (code "63") (name "unconnected-(U4-TX1RTS#-Pad5)") (class "Default")
      (node (ref "U4") (pin "5") (pinfunction "TX1RTS#_5") (pintype "unspecified+no_connect"))
    )
    (net (code "64") (name "unconnected-(U4-TX2RTS#-Pad6)") (class "Default")
      (node (ref "U4") (pin "6") (pinfunction "TX2RTS#_6") (pintype "unspecified+no_connect"))
    )
    (net (code "65") (name "unconnected-(U5-VREF-Pad5)") (class "Default")
      (node (ref "U5") (pin "5") (pinfunction "VREF_5") (pintype "unspecified+no_connect"))
    )
  )
)
